# 06_FPGA_HSIO_B1.net
KiCad netlist of a schematic drawn in Altium Designer
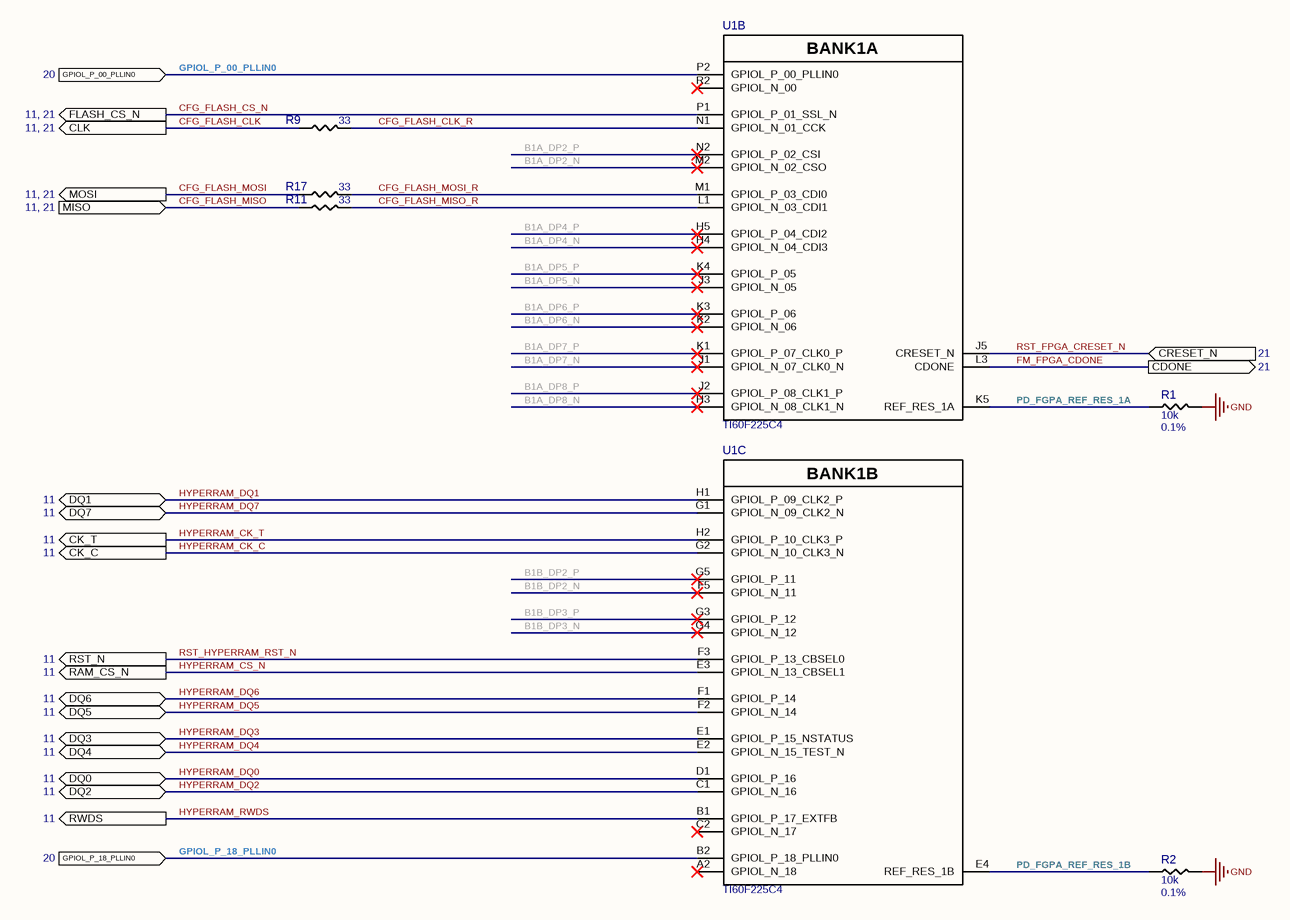
[diagram p0: 06_FPGA_HSIO_B1.SchDoc]

(export (version "E")
  (design (tool "Eeschema 10.0.6"))
  (components
    (comp (ref "R1")
      (value "10k")
      (footprint "RESC1005X03N")
      (description "RES SMD 10K OHM 0.1% 1/16W 0402")
      (fields (field (name "PART NUMBER") "RT0402BRD0710KL") (field (name "TOL") "0.1%"))
      (libsource (lib "Database") (part "Resistor_ENG"))
    )
    (comp (ref "R2")
      (value "10k")
      (footprint "RESC1005X03N")
      (description "RES SMD 10K OHM 0.1% 1/16W 0402")
      (fields (field (name "PART NUMBER") "RT0402BRD0710KL") (field (name "TOL") "0.1%"))
      (libsource (lib "Database") (part "Resistor_ENG"))
    )
    (comp (ref "R9")
      (value "33")
      (footprint "RESC1005X03N")
      (description "RES SMD 33 OHM 1% 1/16W 0402")
      (fields (field (name "PART NUMBER") "RC0402FR-0733RL"))
      (libsource (lib "Database") (part "Resistor_ENG"))
    )
    (comp (ref "R11")
      (value "33")
      (footprint "RESC1005X03N")
      (description "RES SMD 33 OHM 1% 1/16W 0402")
      (fields (field (name "PART NUMBER") "RC0402FR-0733RL"))
      (libsource (lib "Database") (part "Resistor_ENG"))
    )
    (comp (ref "R17")
      (value "33")
      (footprint "RESC1005X03N")
      (description "RES SMD 33 OHM 1% 1/16W 0402")
      (fields (field (name "PART NUMBER") "RC0402FR-0733RL"))
      (libsource (lib "Database") (part "Resistor_ENG"))
    )
    (comp (ref "U1")
      (value "TI60F225C4")
      (footprint "BGA225C65P15X15_1000X1000X100")
      (description "FPGA TITAN 140HSIO 4PLL 225BGA")
      (libsource (lib "Database") (part "TI60F225"))
    )
  )
  (nets
    (net (code "1") (name "/B1A_DP2_N") (class "Default")
      (node (ref "U1") (pin "M2") (pinfunction "GPIOL_N_02_CSO_M2") (pintype "passive+no_connect"))
    )
    (net (code "2") (name "/B1A_DP2_P") (class "Default")
      (node (ref "U1") (pin "N2") (pinfunction "GPIOL_P_02_CSI_N2") (pintype "passive+no_connect"))
    )
    (net (code "3") (name "/B1A_DP4_N") (class "Default")
      (node (ref "U1") (pin "H4") (pinfunction "GPIOL_N_04_CDI3_H4") (pintype "passive+no_connect"))
    )
    (net (code "4") (name "/B1A_DP4_P") (class "Default")
      (node (ref "U1") (pin "H5") (pinfunction "GPIOL_P_04_CDI2_H5") (pintype "passive+no_connect"))
    )
    (net (code "5") (name "/B1A_DP5_N") (class "Default")
      (node (ref "U1") (pin "J3") (pinfunction "GPIOL_N_05_J3") (pintype "passive+no_connect"))
    )
    (net (code "6") (name "/B1A_DP5_P") (class "Default")
      (node (ref "U1") (pin "K4") (pinfunction "GPIOL_P_05_K4") (pintype "passive+no_connect"))
    )
    (net (code "7") (name "/B1A_DP6_N") (class "Default")
      (node (ref "U1") (pin "K2") (pinfunction "GPIOL_N_06_K2") (pintype "passive+no_connect"))
    )
    (net (code "8") (name "/B1A_DP6_P") (class "Default")
      (node (ref "U1") (pin "K3") (pinfunction "GPIOL_P_06_K3") (pintype "passive+no_connect"))
    )
    (net (code "9") (name "/B1A_DP7_N") (class "Default")
      (node (ref "U1") (pin "J1") (pinfunction "GPIOL_N_07_CLK0_N_J1") (pintype "passive+no_connect"))
    )
    (net (code "10") (name "/B1A_DP7_P") (class "Default")
      (node (ref "U1") (pin "K1") (pinfunction "GPIOL_P_07_CLK0_P_K1") (pintype "passive+no_connect"))
    )
    (net (code "11") (name "/B1A_DP8_N") (class "Default")
      (node (ref "U1") (pin "H3") (pinfunction "GPIOL_N_08_CLK1_N_H3") (pintype "passive+no_connect"))
    )
    (net (code "12") (name "/B1A_DP8_P") (class "Default")
      (node (ref "U1") (pin "J2") (pinfunction "GPIOL_P_08_CLK1_P_J2") (pintype "passive+no_connect"))
    )
    (net (code "13") (name "/B1B_DP2_N") (class "Default")
      (node (ref "U1") (pin "F5") (pinfunction "GPIOL_N_11_F5") (pintype "passive+no_connect"))
    )
    (net (code "14") (name "/B1B_DP2_P") (class "Default")
      (node (ref "U1") (pin "G5") (pinfunction "GPIOL_P_11_G5") (pintype "passive+no_connect"))
    )
    (net (code "15") (name "/B1B_DP3_N") (class "Default")
      (node (ref "U1") (pin "G4") (pinfunction "GPIOL_N_12_G4") (pintype "passive+no_connect"))
    )
    (net (code "16") (name "/B1B_DP3_P") (class "Default")
      (node (ref "U1") (pin "G3") (pinfunction "GPIOL_P_12_G3") (pintype "passive+no_connect"))
    )
    (net (code "17") (name "/CFG_FLASH_CLK") (class "Default")
      (node (ref "R9") (pin "1") (pinfunction "1_1") (pintype "passive"))
    )
    (net (code "18") (name "/CFG_FLASH_CLK_R") (class "Default")
      (node (ref "R9") (pin "2") (pinfunction "2_2") (pintype "passive"))
      (node (ref "U1") (pin "N1") (pinfunction "GPIOL_N_01_CCK_N1") (pintype "passive"))
    )
    (net (code "19") (name "/CFG_FLASH_CS_N") (class "Default")
      (node (ref "U1") (pin "P1") (pinfunction "GPIOL_P_01_SSL_N_P1") (pintype "passive"))
    )
    (net (code "20") (name "/CFG_FLASH_MISO") (class "Default")
      (node (ref "R11") (pin "1") (pinfunction "1_1") (pintype "passive"))
    )
    (net (code "21") (name "/CFG_FLASH_MISO_R") (class "Default")
      (node (ref "R11") (pin "2") (pinfunction "2_2") (pintype "passive"))
      (node (ref "U1") (pin "L1") (pinfunction "GPIOL_N_03_CDI1_L1") (pintype "passive"))
    )
    (net (code "22") (name "/CFG_FLASH_MOSI") (class "Default")
      (node (ref "R17") (pin "1") (pinfunction "1_1") (pintype "passive"))
    )
    (net (code "23") (name "/CFG_FLASH_MOSI_R") (class "Default")
      (node (ref "R17") (pin "2") (pinfunction "2_2") (pintype "passive"))
      (node (ref "U1") (pin "M1") (pinfunction "GPIOL_P_03_CDI0_M1") (pintype "passive"))
    )
    (net (code "24") (name "/FM_FPGA_CDONE") (class "Default")
      (node (ref "U1") (pin "L3") (pinfunction "CDONE_L3") (pintype "passive"))
    )
    (net (code "25") (name "/GPIOL_P_00_PLLIN0") (class "Default")
      (node (ref "U1") (pin "P2") (pinfunction "GPIOL_P_00_PLLIN0_P2") (pintype "passive"))
    )
    (net (code "26") (name "/GPIOL_P_18_PLLIN0") (class "Default")
      (node (ref "U1") (pin "B2") (pinfunction "GPIOL_P_18_PLLIN0_B2") (pintype "passive"))
    )
    (net (code "27") (name "/HYPERRAM_CK_C") (class "Default")
      (node (ref "U1") (pin "G2") (pinfunction "GPIOL_N_10_CLK3_N_G2") (pintype "passive"))
    )
    (net (code "28") (name "/HYPERRAM_CK_T") (class "Default")
      (node (ref "U1") (pin "H2") (pinfunction "GPIOL_P_10_CLK3_P_H2") (pintype "passive"))
    )
    (net (code "29") (name "/HYPERRAM_CS_N") (class "Default")
      (node (ref "U1") (pin "E3") (pinfunction "GPIOL_N_13_CBSEL1_E3") (pintype "passive"))
    )
    (net (code "30") (name "/HYPERRAM_DQ0") (class "Default")
      (node (ref "U1") (pin "D1") (pinfunction "GPIOL_P_16_D1") (pintype "passive"))
    )
    (net (code "31") (name "/HYPERRAM_DQ1") (class "Default")
      (node (ref "U1") (pin "H1") (pinfunction "GPIOL_P_09_CLK2_P_H1") (pintype "passive"))
    )
    (net (code "32") (name "/HYPERRAM_DQ2") (class "Default")
      (node (ref "U1") (pin "C1") (pinfunction "GPIOL_N_16_C1") (pintype "passive"))
    )
    (net (code "33") (name "/HYPERRAM_DQ3") (class "Default")
      (node (ref "U1") (pin "E1") (pinfunction "GPIOL_P_15_NSTATUS_E1") (pintype "passive"))
    )
    (net (code "34") (name "/HYPERRAM_DQ4") (class "Default")
      (node (ref "U1") (pin "E2") (pinfunction "GPIOL_N_15_TEST_N_E2") (pintype "passive"))
    )
    (net (code "35") (name "/HYPERRAM_DQ5") (class "Default")
      (node (ref "U1") (pin "F2") (pinfunction "GPIOL_N_14_F2") (pintype "passive"))
    )
    (net (code "36") (name "/HYPERRAM_DQ6") (class "Default")
      (node (ref "U1") (pin "F1") (pinfunction "GPIOL_P_14_F1") (pintype "passive"))
    )
    (net (code "37") (name "/HYPERRAM_DQ7") (class "Default")
      (node (ref "U1") (pin "G1") (pinfunction "GPIOL_N_09_CLK2_N_G1") (pintype "passive"))
    )
    (net (code "38") (name "/HYPERRAM_RWDS") (class "Default")
      (node (ref "U1") (pin "B1") (pinfunction "GPIOL_P_17_EXTFB_B1") (pintype "passive"))
    )
    (net (code "39") (name "/PD_FGPA_REF_RES_1A") (class "Default")
      (node (ref "R1") (pin "1") (pinfunction "1_1") (pintype "passive"))
      (node (ref "U1") (pin "K5") (pinfunction "REF_RES_1A_K5") (pintype "passive"))
    )
    (net (code "40") (name "/PD_FGPA_REF_RES_1B") (class "Default")
      (node (ref "R2") (pin "1") (pinfunction "1_1") (pintype "passive"))
      (node (ref "U1") (pin "E4") (pinfunction "REF_RES_1B_E4") (pintype "passive"))
    )
    (net (code "41") (name "/RST_FPGA_CRESET_N") (class "Default")
      (node (ref "U1") (pin "J5") (pinfunction "CRESET_N_J5") (pintype "passive"))
    )
    (net (code "42") (name "/RST_HYPERRAM_RST_N") (class "Default")
      (node (ref "U1") (pin "F3") (pinfunction "GPIOL_P_13_CBSEL0_F3") (pintype "passive"))
    )
    (net (code "43") (name "GND") (class "Default")
      (node (ref "R1") (pin "2") (pinfunction "2_2") (pintype "passive"))
      (node (ref "R2") (pin "2") (pinfunction "2_2") (pintype "passive"))
    )
    (net (code "44") (name "unconnected-(U1B-GPIOL_N_00-PadR2)") (class "Default")
      (node (ref "U1") (pin "R2") (pinfunction "GPIOL_N_00_R2") (pintype "passive+no_connect"))
    )
    (net (code "45") (name "unconnected-(U1C-GPIOL_N_17-PadC2)") (class "Default")
      (node (ref "U1") (pin "C2") (pinfunction "GPIOL_N_17_C2") (pintype "passive+no_connect"))
    )
    (net (code "46") (name "unconnected-(U1C-GPIOL_N_18-PadA2)") (class "Default")
      (node (ref "U1") (pin "A2") (pinfunction "GPIOL_N_18_A2") (pintype "passive+no_connect"))
    )
  )
)
